# Dancarino.net
KiCad netlist of a schematic drawn in EAGLE
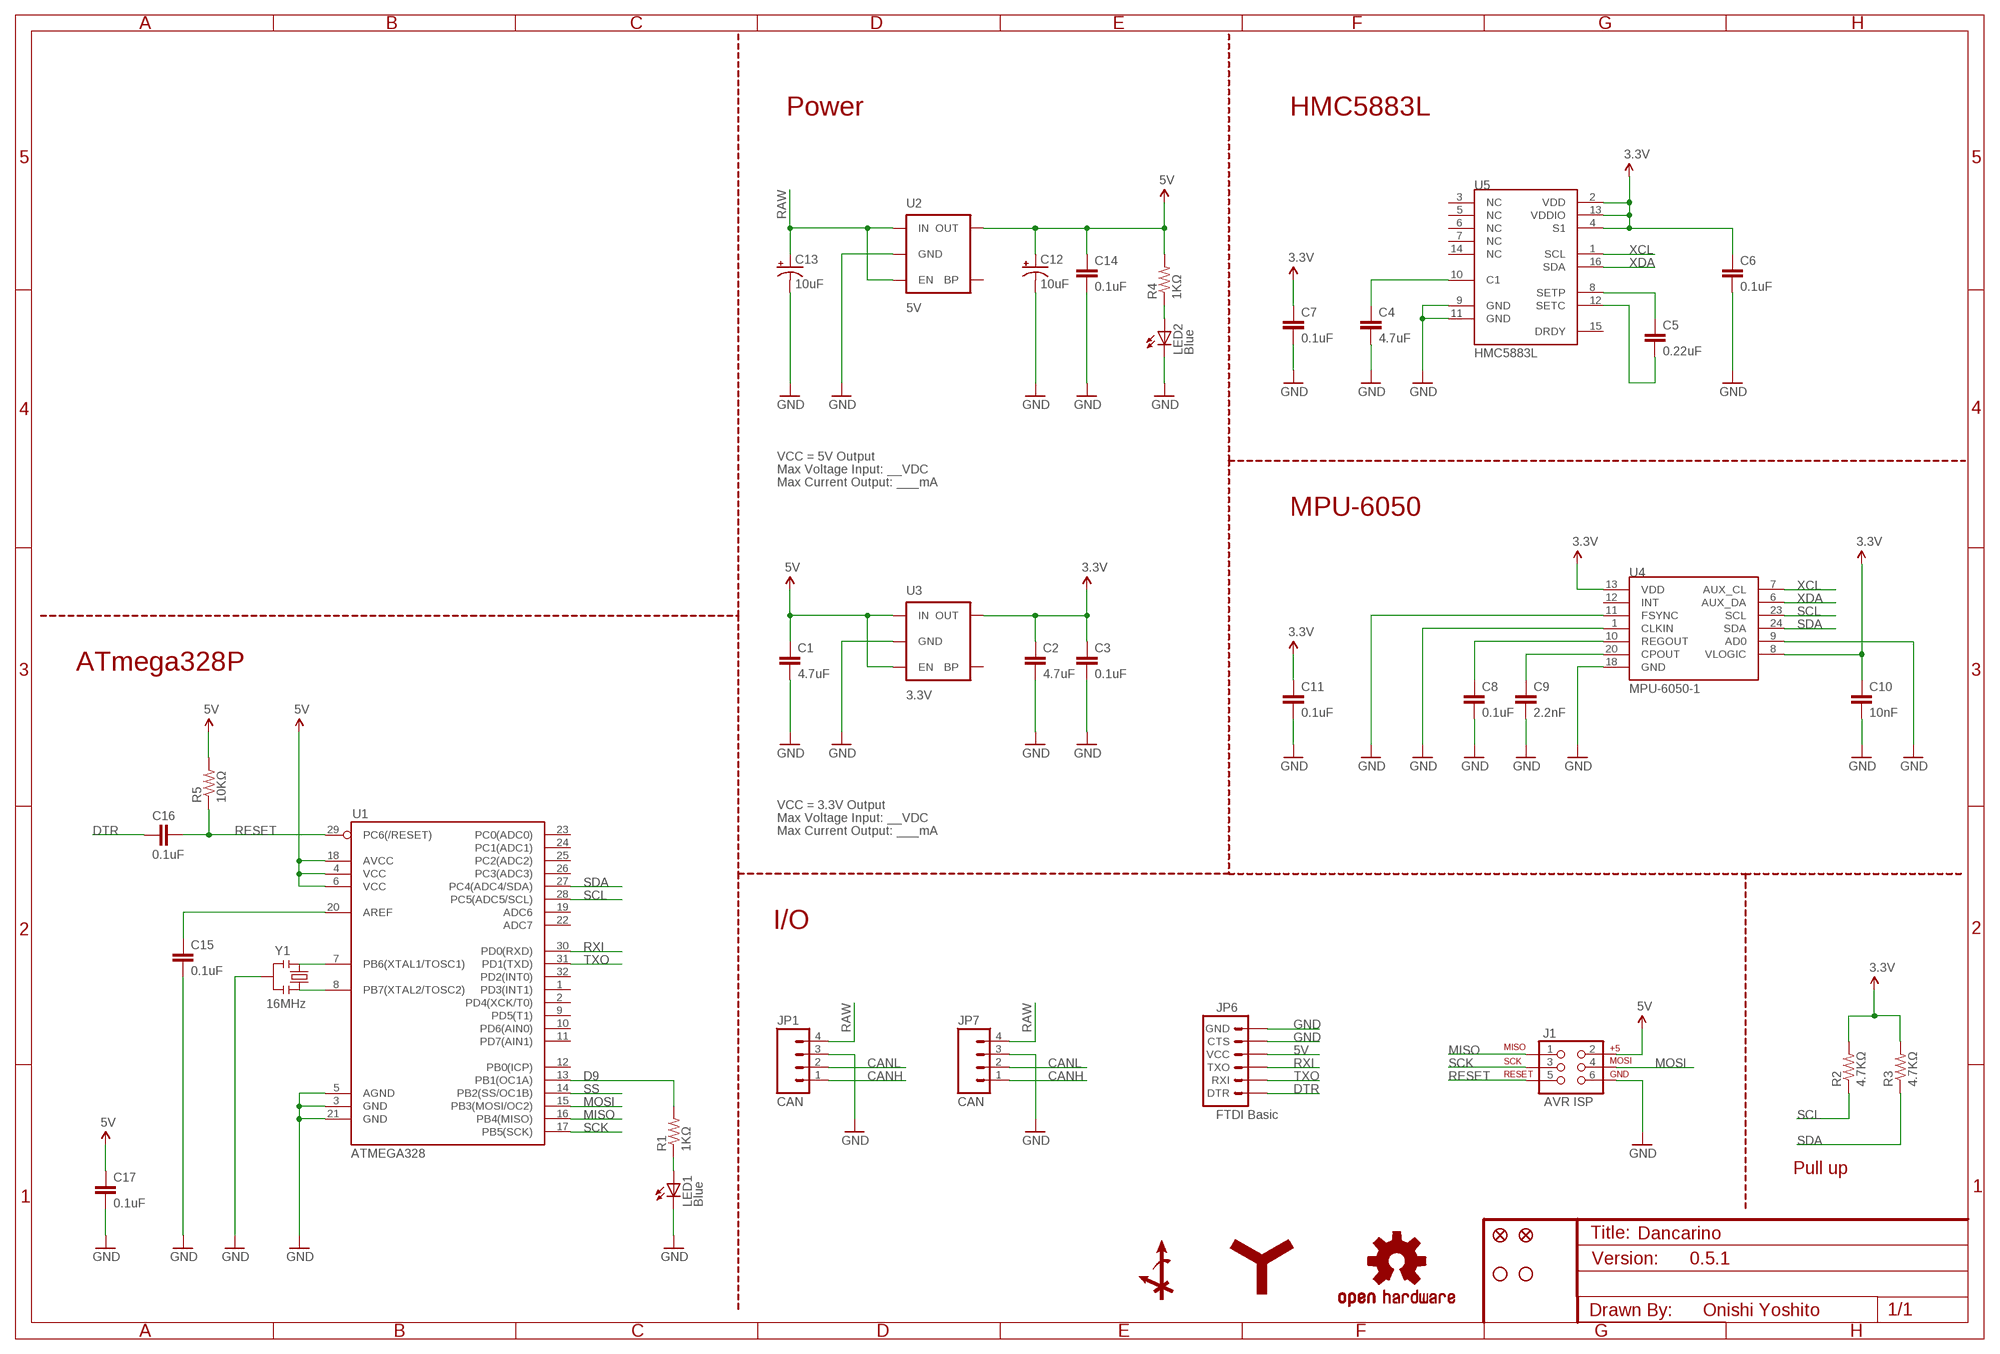
[diagram p0: schematic, sheet 1]

(export (version "E")
  (design (tool "Eeschema 10.0.6"))
  (components
    (comp (ref "C1")
      (value "4.7uF")
      (footprint "eagle-import:0402-CAP")
      (libsource (lib "eagle-import") (part "CAP0402-CAP"))
    )
    (comp (ref "C2")
      (value "4.7uF")
      (footprint "eagle-import:0402-CAP")
      (libsource (lib "eagle-import") (part "CAP0402-CAP"))
    )
    (comp (ref "C3")
      (value "0.1uF")
      (footprint "eagle-import:0402-CAP")
      (libsource (lib "eagle-import") (part "CAP0402-CAP"))
    )
    (comp (ref "C4")
      (value "4.7uF")
      (footprint "eagle-import:0402-CAP")
      (libsource (lib "eagle-import") (part "CAP0402-CAP"))
    )
    (comp (ref "C5")
      (value "0.22uF")
      (footprint "eagle-import:0402-CAP")
      (libsource (lib "eagle-import") (part "CAP0402-CAP"))
    )
    (comp (ref "C6")
      (value "0.1uF")
      (footprint "eagle-import:0402-CAP")
      (libsource (lib "eagle-import") (part "CAP0402-CAP"))
    )
    (comp (ref "C7")
      (value "0.1uF")
      (footprint "eagle-import:0402-CAP")
      (libsource (lib "eagle-import") (part "CAP0402-CAP"))
    )
    (comp (ref "C8")
      (value "0.1uF")
      (footprint "eagle-import:0402-CAP")
      (libsource (lib "eagle-import") (part "CAP0402-CAP"))
    )
    (comp (ref "C9")
      (value "2.2nF")
      (footprint "eagle-import:0402-CAP")
      (libsource (lib "eagle-import") (part "CAP0402-CAP"))
    )
    (comp (ref "C10")
      (value "10nF")
      (footprint "eagle-import:0402-CAP")
      (libsource (lib "eagle-import") (part "CAP0402-CAP"))
    )
    (comp (ref "C11")
      (value "0.1uF")
      (footprint "eagle-import:0402-CAP")
      (libsource (lib "eagle-import") (part "CAP0402-CAP"))
    )
    (comp (ref "C12")
      (value "10uF")
      (footprint "eagle-import:EIA3216")
      (libsource (lib "eagle-import") (part "CAP_POL1206"))
    )
    (comp (ref "C13")
      (value "10uF")
      (footprint "eagle-import:EIA3216")
      (libsource (lib "eagle-import") (part "CAP_POL1206"))
    )
    (comp (ref "C14")
      (value "0.1uF")
      (footprint "eagle-import:0402-CAP")
      (libsource (lib "eagle-import") (part "CAP0402-CAP"))
    )
    (comp (ref "C15")
      (value "0.1uF")
      (footprint "eagle-import:0402-CAP")
      (libsource (lib "eagle-import") (part "CAP0402-CAP"))
    )
    (comp (ref "C16")
      (value "0.1uF")
      (footprint "eagle-import:0402-CAP")
      (libsource (lib "eagle-import") (part "CAP0402-CAP"))
    )
    (comp (ref "C17")
      (value "0.1uF")
      (footprint "eagle-import:0402-CAP")
      (libsource (lib "eagle-import") (part "CAP0402-CAP"))
    )
    (comp (ref "J1")
      (value "AVR ISP")
      (footprint "eagle-import:2X3-NS")
      (libsource (lib "eagle-import") (part "AVR_SPI_PRG_6NS"))
    )
    (comp (ref "JP1")
      (value "CAN")
      (footprint "eagle-import:JST-4-PTH")
      (libsource (lib "eagle-import") (part "M04JST-PTH"))
    )
    (comp (ref "JP2")
      (value "FIDUCIALUFIDUCIAL")
      (footprint "eagle-import:MICRO-FIDUCIAL")
      (libsource (lib "eagle-import") (part "FIDUCIALUFIDUCIAL"))
    )
    (comp (ref "JP3")
      (value "STAND-OFFTIGHT")
      (footprint "eagle-import:STAND-OFF-TIGHT")
      (libsource (lib "eagle-import") (part "STAND-OFFTIGHT"))
    )
    (comp (ref "JP4")
      (value "STAND-OFFTIGHT")
      (footprint "eagle-import:STAND-OFF-TIGHT")
      (libsource (lib "eagle-import") (part "STAND-OFFTIGHT"))
    )
    (comp (ref "JP5")
      (value "FIDUCIALUFIDUCIAL")
      (footprint "eagle-import:MICRO-FIDUCIAL")
      (libsource (lib "eagle-import") (part "FIDUCIALUFIDUCIAL"))
    )
    (comp (ref "JP6")
      (value "FTDI Basic")
      (footprint "eagle-import:1X06")
      (libsource (lib "eagle-import") (part "ARDUINO_SERIAL_PROGRAMPTH"))
    )
    (comp (ref "JP7")
      (value "CAN")
      (footprint "eagle-import:JST-4-PTH")
      (libsource (lib "eagle-import") (part "M04JST-PTH"))
    )
    (comp (ref "LED1")
      (value "Blue")
      (footprint "eagle-import:LED-0603")
      (libsource (lib "eagle-import") (part "LED0603"))
    )
    (comp (ref "LED2")
      (value "Blue")
      (footprint "eagle-import:LED-0603")
      (libsource (lib "eagle-import") (part "LED0603"))
    )
    (comp (ref "R1")
      (value "1KΩ")
      (footprint "eagle-import:0402-RES")
      (libsource (lib "eagle-import") (part "RESISTOR0402-RES"))
    )
    (comp (ref "R2")
      (value "4.7KΩ")
      (footprint "eagle-import:0402-RES")
      (libsource (lib "eagle-import") (part "RESISTOR0402-RES"))
    )
    (comp (ref "R3")
      (value "4.7KΩ")
      (footprint "eagle-import:0402-RES")
      (libsource (lib "eagle-import") (part "RESISTOR0402-RES"))
    )
    (comp (ref "R4")
      (value "1KΩ")
      (footprint "eagle-import:0402-RES")
      (libsource (lib "eagle-import") (part "RESISTOR0402-RES"))
    )
    (comp (ref "R5")
      (value "10KΩ")
      (footprint "eagle-import:0402-RES")
      (libsource (lib "eagle-import") (part "RESISTOR0402-RES"))
    )
    (comp (ref "U$2")
      (value "OSHW-LOGOS")
      (footprint "eagle-import:OSHW-LOGO-S")
      (libsource (lib "eagle-import") (part "OSHW-LOGOS"))
    )
    (comp (ref "U$11")
      (value "AXIS-ANGLE_S")
      (footprint "eagle-import:AXIS-ANGLE_S")
      (libsource (lib "eagle-import") (part "AXIS-ANGLE_S"))
    )
    (comp (ref "U$13")
      (value "YCAM_LOGO_L")
      (footprint "eagle-import:YCAM_LOGO_L")
      (libsource (lib "eagle-import") (part "YCAM_LOGO_L"))
    )
    (comp (ref "U1")
      (value "ATMEGA328")
      (footprint "eagle-import:TQFP32-08")
      (libsource (lib "eagle-import") (part "ATMEGA168"))
    )
    (comp (ref "U2")
      (value "5V")
      (footprint "eagle-import:SOT23-5")
      (libsource (lib "eagle-import") (part "V_REG_LDOSMD"))
    )
    (comp (ref "U3")
      (value "3.3V")
      (footprint "eagle-import:SOT23-5")
      (libsource (lib "eagle-import") (part "V_REG_LDOSMD"))
    )
    (comp (ref "U4")
      (value "MPU-6050-1")
      (footprint "eagle-import:QFN-24-4MM2")
      (libsource (lib "eagle-import") (part "MPU-6050-1"))
    )
    (comp (ref "U5")
      (value "HMC5883L")
      (footprint "eagle-import:16LPCC")
      (libsource (lib "eagle-import") (part "HMC5883LSMD"))
    )
    (comp (ref "Y1")
      (value "16MHz")
      (footprint "eagle-import:RESONATOR-SMD")
      (libsource (lib "eagle-import") (part "RESONATORSMD"))
    )
  )
  (nets
    (net (code "1") (name "/CANH") (class "Default")
      (node (ref "JP1") (pin "1") (pinfunction "1_1") (pintype "passive"))
      (node (ref "JP7") (pin "1") (pinfunction "1_1") (pintype "passive"))
    )
    (net (code "2") (name "/CANL") (class "Default")
      (node (ref "JP1") (pin "2") (pinfunction "2_2") (pintype "passive"))
      (node (ref "JP7") (pin "2") (pinfunction "2_2") (pintype "passive"))
    )
    (net (code "3") (name "/D9") (class "Default")
      (node (ref "R1") (pin "2") (pinfunction "2_2") (pintype "passive"))
      (node (ref "U1") (pin "13") (pinfunction "PB1(OC1A)_13") (pintype "bidirectional"))
    )
    (net (code "4") (name "/DTR") (class "Default")
      (node (ref "C16") (pin "1") (pinfunction "1_1") (pintype "passive"))
      (node (ref "JP6") (pin "1") (pinfunction "DTR_1") (pintype "passive"))
    )
    (net (code "5") (name "/MISO") (class "Default")
      (node (ref "J1") (pin "1") (pinfunction "1_1") (pintype "passive"))
      (node (ref "U1") (pin "16") (pinfunction "PB4(MISO)_16") (pintype "bidirectional"))
    )
    (net (code "6") (name "/MOSI") (class "Default")
      (node (ref "J1") (pin "4") (pinfunction "4_4") (pintype "passive"))
      (node (ref "U1") (pin "15") (pinfunction "PB3(MOSI/OC2)_15") (pintype "bidirectional"))
    )
    (net (code "7") (name "/RAW") (class "Default")
      (node (ref "C13") (pin "A") (pinfunction "+_A") (pintype "passive"))
      (node (ref "JP1") (pin "4") (pinfunction "4_4") (pintype "passive"))
      (node (ref "JP7") (pin "4") (pinfunction "4_4") (pintype "passive"))
      (node (ref "U2") (pin "1") (pinfunction "IN_1") (pintype "input"))
      (node (ref "U2") (pin "3") (pinfunction "EN_3") (pintype "input"))
    )
    (net (code "8") (name "/RESET") (class "Default")
      (node (ref "C16") (pin "2") (pinfunction "2_2") (pintype "passive"))
      (node (ref "J1") (pin "5") (pinfunction "5_5") (pintype "passive"))
      (node (ref "R5") (pin "1") (pinfunction "1_1") (pintype "passive"))
      (node (ref "U1") (pin "29") (pinfunction "PC6(/RESET)_29") (pintype "bidirectional"))
    )
    (net (code "9") (name "/RXI") (class "Default")
      (node (ref "JP6") (pin "3") (pinfunction "TXO_3") (pintype "passive"))
      (node (ref "U1") (pin "30") (pinfunction "PD0(RXD)_30") (pintype "bidirectional"))
    )
    (net (code "10") (name "/SCK") (class "Default")
      (node (ref "J1") (pin "3") (pinfunction "3_3") (pintype "passive"))
      (node (ref "U1") (pin "17") (pinfunction "PB5(SCK)_17") (pintype "bidirectional"))
    )
    (net (code "11") (name "/SCL") (class "Default")
      (node (ref "R2") (pin "1") (pinfunction "1_1") (pintype "passive"))
      (node (ref "U1") (pin "28") (pinfunction "PC5(ADC5/SCL)_28") (pintype "bidirectional"))
      (node (ref "U4") (pin "23") (pinfunction "SCL_23") (pintype "bidirectional"))
    )
    (net (code "12") (name "/SDA") (class "Default")
      (node (ref "R3") (pin "1") (pinfunction "1_1") (pintype "passive"))
      (node (ref "U1") (pin "27") (pinfunction "PC4(ADC4/SDA)_27") (pintype "bidirectional"))
      (node (ref "U4") (pin "24") (pinfunction "SDA_24") (pintype "bidirectional"))
    )
    (net (code "13") (name "/SS") (class "Default")
      (node (ref "U1") (pin "14") (pinfunction "PB2(SS/OC1B)_14") (pintype "bidirectional"))
    )
    (net (code "14") (name "/TXO") (class "Default")
      (node (ref "JP6") (pin "2") (pinfunction "RXI_2") (pintype "passive"))
      (node (ref "U1") (pin "31") (pinfunction "PD1(TXD)_31") (pintype "bidirectional"))
    )
    (net (code "15") (name "/XCL") (class "Default")
      (node (ref "U4") (pin "7") (pinfunction "AUX_CL_7") (pintype "bidirectional"))
      (node (ref "U5") (pin "1") (pinfunction "SCL_1") (pintype "bidirectional"))
    )
    (net (code "16") (name "/XDA") (class "Default")
      (node (ref "U4") (pin "6") (pinfunction "AUX_DA_6") (pintype "bidirectional"))
      (node (ref "U5") (pin "16") (pinfunction "SDA_16") (pintype "bidirectional"))
    )
    (net (code "17") (name "3.3V") (class "Default")
      (node (ref "C10") (pin "1") (pinfunction "1_1") (pintype "passive"))
      (node (ref "C11") (pin "1") (pinfunction "1_1") (pintype "passive"))
      (node (ref "C2") (pin "1") (pinfunction "1_1") (pintype "passive"))
      (node (ref "C3") (pin "1") (pinfunction "1_1") (pintype "passive"))
      (node (ref "C6") (pin "1") (pinfunction "1_1") (pintype "passive"))
      (node (ref "C7") (pin "1") (pinfunction "1_1") (pintype "passive"))
      (node (ref "R2") (pin "2") (pinfunction "2_2") (pintype "passive"))
      (node (ref "R3") (pin "2") (pinfunction "2_2") (pintype "passive"))
      (node (ref "U3") (pin "5") (pinfunction "OUT_5") (pintype "passive"))
      (node (ref "U4") (pin "13") (pinfunction "VDD_13") (pintype "bidirectional"))
      (node (ref "U4") (pin "8") (pinfunction "VLOGIC_8") (pintype "bidirectional"))
      (node (ref "U5") (pin "13") (pinfunction "VDDIO_13") (pintype "bidirectional"))
      (node (ref "U5") (pin "2") (pinfunction "VDD_2") (pintype "bidirectional"))
      (node (ref "U5") (pin "4") (pinfunction "S1_4") (pintype "bidirectional"))
    )
    (net (code "18") (name "5V") (class "Default")
      (node (ref "C1") (pin "1") (pinfunction "1_1") (pintype "passive"))
      (node (ref "C12") (pin "A") (pinfunction "+_A") (pintype "passive"))
      (node (ref "C14") (pin "1") (pinfunction "1_1") (pintype "passive"))
      (node (ref "C17") (pin "1") (pinfunction "1_1") (pintype "passive"))
      (node (ref "J1") (pin "2") (pinfunction "2_2") (pintype "passive"))
      (node (ref "JP6") (pin "4") (pinfunction "VCC_4") (pintype "passive"))
      (node (ref "R4") (pin "2") (pinfunction "2_2") (pintype "passive"))
      (node (ref "R5") (pin "2") (pinfunction "2_2") (pintype "passive"))
      (node (ref "U1") (pin "18") (pinfunction "AVCC_18") (pintype "bidirectional"))
      (node (ref "U1") (pin "4") (pinfunction "VCC_4") (pintype "bidirectional"))
      (node (ref "U1") (pin "6") (pinfunction "VCC_6") (pintype "bidirectional"))
      (node (ref "U2") (pin "5") (pinfunction "OUT_5") (pintype "passive"))
      (node (ref "U3") (pin "1") (pinfunction "IN_1") (pintype "input"))
      (node (ref "U3") (pin "3") (pinfunction "EN_3") (pintype "input"))
    )
    (net (code "19") (name "GND") (class "Default")
      (node (ref "C1") (pin "2") (pinfunction "2_2") (pintype "passive"))
      (node (ref "C10") (pin "2") (pinfunction "2_2") (pintype "passive"))
      (node (ref "C11") (pin "2") (pinfunction "2_2") (pintype "passive"))
      (node (ref "C12") (pin "C") (pinfunction "-_C") (pintype "passive"))
      (node (ref "C13") (pin "C") (pinfunction "-_C") (pintype "passive"))
      (node (ref "C14") (pin "2") (pinfunction "2_2") (pintype "passive"))
      (node (ref "C15") (pin "2") (pinfunction "2_2") (pintype "passive"))
      (node (ref "C17") (pin "2") (pinfunction "2_2") (pintype "passive"))
      (node (ref "C2") (pin "2") (pinfunction "2_2") (pintype "passive"))
      (node (ref "C3") (pin "2") (pinfunction "2_2") (pintype "passive"))
      (node (ref "C4") (pin "2") (pinfunction "2_2") (pintype "passive"))
      (node (ref "C6") (pin "2") (pinfunction "2_2") (pintype "passive"))
      (node (ref "C7") (pin "2") (pinfunction "2_2") (pintype "passive"))
      (node (ref "C8") (pin "2") (pinfunction "2_2") (pintype "passive"))
      (node (ref "C9") (pin "2") (pinfunction "2_2") (pintype "passive"))
      (node (ref "J1") (pin "6") (pinfunction "6_6") (pintype "passive"))
      (node (ref "JP1") (pin "3") (pinfunction "3_3") (pintype "passive"))
      (node (ref "JP6") (pin "5") (pinfunction "CTS_5") (pintype "passive"))
      (node (ref "JP6") (pin "6") (pinfunction "GND_6") (pintype "passive"))
      (node (ref "JP7") (pin "3") (pinfunction "3_3") (pintype "passive"))
      (node (ref "LED1") (pin "C") (pinfunction "C_C") (pintype "passive"))
      (node (ref "LED2") (pin "C") (pinfunction "C_C") (pintype "passive"))
      (node (ref "U1") (pin "21") (pinfunction "GND_21") (pintype "bidirectional"))
      (node (ref "U1") (pin "3") (pinfunction "GND_3") (pintype "bidirectional"))
      (node (ref "U1") (pin "5") (pinfunction "AGND_5") (pintype "bidirectional"))
      (node (ref "U2") (pin "2") (pinfunction "GND_2") (pintype "input"))
      (node (ref "U3") (pin "2") (pinfunction "GND_2") (pintype "input"))
      (node (ref "U4") (pin "1") (pinfunction "CLKIN_1") (pintype "bidirectional"))
      (node (ref "U4") (pin "11") (pinfunction "FSYNC_11") (pintype "bidirectional"))
      (node (ref "U4") (pin "18") (pinfunction "GND_18") (pintype "bidirectional"))
      (node (ref "U4") (pin "9") (pinfunction "AD0_9") (pintype "bidirectional"))
      (node (ref "U5") (pin "11") (pinfunction "GND_11") (pintype "bidirectional"))
      (node (ref "U5") (pin "9") (pinfunction "GND_9") (pintype "bidirectional"))
      (node (ref "Y1") (pin "2") (pinfunction "2_2") (pintype "passive"))
    )
    (net (code "20") (name "Net-(LED1-PadA)") (class "Default")
      (node (ref "LED1") (pin "A") (pinfunction "A_A") (pintype "passive"))
      (node (ref "R1") (pin "1") (pinfunction "1_1") (pintype "passive"))
    )
    (net (code "21") (name "Net-(LED2-PadA)") (class "Default")
      (node (ref "LED2") (pin "A") (pinfunction "A_A") (pintype "passive"))
      (node (ref "R4") (pin "1") (pinfunction "1_1") (pintype "passive"))
    )
    (net (code "22") (name "Net-(U1-AREF)") (class "Default")
      (node (ref "C15") (pin "1") (pinfunction "1_1") (pintype "passive"))
      (node (ref "U1") (pin "20") (pinfunction "AREF_20") (pintype "bidirectional"))
    )
    (net (code "23") (name "Net-(U1-PB6(XTAL1{slash}TOSC1))") (class "Default")
      (node (ref "U1") (pin "7") (pinfunction "PB6(XTAL1/TOSC1)_7") (pintype "bidirectional"))
      (node (ref "Y1") (pin "1") (pinfunction "1_1") (pintype "passive"))
    )
    (net (code "24") (name "Net-(U1-PB7(XTAL2{slash}TOSC2))") (class "Default")
      (node (ref "U1") (pin "8") (pinfunction "PB7(XTAL2/TOSC2)_8") (pintype "bidirectional"))
      (node (ref "Y1") (pin "3") (pinfunction "3_3") (pintype "passive"))
    )
    (net (code "25") (name "Net-(U4-CPOUT)") (class "Default")
      (node (ref "C9") (pin "1") (pinfunction "1_1") (pintype "passive"))
      (node (ref "U4") (pin "20") (pinfunction "CPOUT_20") (pintype "bidirectional"))
    )
    (net (code "26") (name "Net-(U4-REGOUT)") (class "Default")
      (node (ref "C8") (pin "1") (pinfunction "1_1") (pintype "passive"))
      (node (ref "U4") (pin "10") (pinfunction "REGOUT_10") (pintype "bidirectional"))
    )
    (net (code "27") (name "Net-(U5-C1)") (class "Default")
      (node (ref "C4") (pin "1") (pinfunction "1_1") (pintype "passive"))
      (node (ref "U5") (pin "10") (pinfunction "C1_10") (pintype "bidirectional"))
    )
    (net (code "28") (name "Net-(U5-SETC)") (class "Default")
      (node (ref "C5") (pin "2") (pinfunction "2_2") (pintype "passive"))
      (node (ref "U5") (pin "12") (pinfunction "SETC_12") (pintype "bidirectional"))
    )
    (net (code "29") (name "Net-(U5-SETP)") (class "Default")
      (node (ref "C5") (pin "1") (pinfunction "1_1") (pintype "passive"))
      (node (ref "U5") (pin "8") (pinfunction "SETP_8") (pintype "bidirectional"))
    )
    (net (code "30") (name "unconnected-(U1-ADC6-Pad19)") (class "Default")
      (node (ref "U1") (pin "19") (pinfunction "ADC6_19") (pintype "bidirectional"))
    )
    (net (code "31") (name "unconnected-(U1-ADC7-Pad22)") (class "Default")
      (node (ref "U1") (pin "22") (pinfunction "ADC7_22") (pintype "bidirectional"))
    )
    (net (code "32") (name "unconnected-(U1-PB0(ICP)-Pad12)") (class "Default")
      (node (ref "U1") (pin "12") (pinfunction "PB0(ICP)_12") (pintype "bidirectional"))
    )
    (net (code "33") (name "unconnected-(U1-PC0(ADC0)-Pad23)") (class "Default")
      (node (ref "U1") (pin "23") (pinfunction "PC0(ADC0)_23") (pintype "bidirectional"))
    )
    (net (code "34") (name "unconnected-(U1-PC1(ADC1)-Pad24)") (class "Default")
      (node (ref "U1") (pin "24") (pinfunction "PC1(ADC1)_24") (pintype "bidirectional"))
    )
    (net (code "35") (name "unconnected-(U1-PC2(ADC2)-Pad25)") (class "Default")
      (node (ref "U1") (pin "25") (pinfunction "PC2(ADC2)_25") (pintype "bidirectional"))
    )
    (net (code "36") (name "unconnected-(U1-PC3(ADC3)-Pad26)") (class "Default")
      (node (ref "U1") (pin "26") (pinfunction "PC3(ADC3)_26") (pintype "bidirectional"))
    )
    (net (code "37") (name "unconnected-(U1-PD2(INT0)-Pad32)") (class "Default")
      (node (ref "U1") (pin "32") (pinfunction "PD2(INT0)_32") (pintype "bidirectional"))
    )
    (net (code "38") (name "unconnected-(U1-PD3(INT1)-Pad1)") (class "Default")
      (node (ref "U1") (pin "1") (pinfunction "PD3(INT1)_1") (pintype "bidirectional"))
    )
    (net (code "39") (name "unconnected-(U1-PD4(XCK{slash}T0)-Pad2)") (class "Default")
      (node (ref "U1") (pin "2") (pinfunction "PD4(XCK/T0)_2") (pintype "bidirectional"))
    )
    (net (code "40") (name "unconnected-(U1-PD5(T1)-Pad9)") (class "Default")
      (node (ref "U1") (pin "9") (pinfunction "PD5(T1)_9") (pintype "bidirectional"))
    )
    (net (code "41") (name "unconnected-(U1-PD6(AIN0)-Pad10)") (class "Default")
      (node (ref "U1") (pin "10") (pinfunction "PD6(AIN0)_10") (pintype "bidirectional"))
    )
    (net (code "42") (name "unconnected-(U1-PD7(AIN1)-Pad11)") (class "Default")
      (node (ref "U1") (pin "11") (pinfunction "PD7(AIN1)_11") (pintype "bidirectional"))
    )
    (net (code "43") (name "unconnected-(U2-BP-Pad4)") (class "Default")
      (node (ref "U2") (pin "4") (pinfunction "BP_4") (pintype "input"))
    )
    (net (code "44") (name "unconnected-(U3-BP-Pad4)") (class "Default")
      (node (ref "U3") (pin "4") (pinfunction "BP_4") (pintype "input"))
    )
    (net (code "45") (name "unconnected-(U4-INT-Pad12)") (class "Default")
      (node (ref "U4") (pin "12") (pinfunction "INT_12") (pintype "bidirectional"))
    )
    (net (code "46") (name "unconnected-(U5-DRDY-Pad15)") (class "Default")
      (node (ref "U5") (pin "15") (pinfunction "DRDY_15") (pintype "bidirectional"))
    )
    (net (code "47") (name "unconnected-(U5-NC-Pad3)") (class "Default")
      (node (ref "U5") (pin "3") (pinfunction "NC_3") (pintype "bidirectional"))
    )
    (net (code "48") (name "unconnected-(U5-NC-Pad5)") (class "Default")
      (node (ref "U5") (pin "5") (pinfunction "NC_5") (pintype "bidirectional"))
    )
    (net (code "49") (name "unconnected-(U5-NC-Pad6)") (class "Default")
      (node (ref "U5") (pin "6") (pinfunction "NC_6") (pintype "bidirectional"))
    )
    (net (code "50") (name "unconnected-(U5-NC-Pad7)") (class "Default")
      (node (ref "U5") (pin "7") (pinfunction "NC_7") (pintype "bidirectional"))
    )
    (net (code "51") (name "unconnected-(U5-NC-Pad14)") (class "Default")
      (node (ref "U5") (pin "14") (pinfunction "NC_14") (pintype "bidirectional"))
    )
  )
)
